# convertor_board.net
KiCad netlist of a schematic drawn in EAGLE
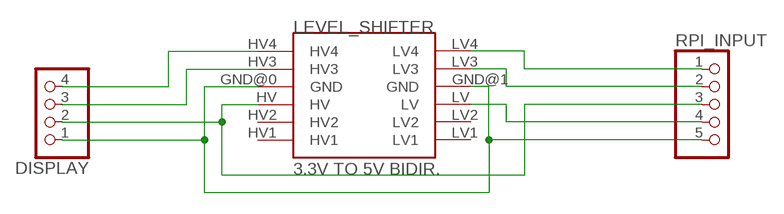
[diagram p0: schematic, sheet 1]

(export (version "E")
  (design (tool "Eeschema 10.0.6"))
  (components
    (comp (ref "DISPLAY")
      (value "PINHD-1X4")
      (footprint "eagle-import:1X04")
      (libsource (lib "eagle-import") (part "PINHD-1X4"))
    )
    (comp (ref "LEVEL_SHIFTER")
      (value "3.3V TO 5V BIDIR.")
      (footprint "eagle-import:LEVEL_SHIFTER")
      (libsource (lib "eagle-import") (part "LEVEL_SHIFTER"))
    )
    (comp (ref "RPI_INPUT")
      (value "PINHD-1X5")
      (footprint "eagle-import:1X05")
      (libsource (lib "eagle-import") (part "PINHD-1X5"))
    )
  )
  (nets
    (net (code "1") (name "Net-(DISPLAY-Pad1)") (class "Default")
      (node (ref "DISPLAY") (pin "1") (pinfunction "1_1") (pintype "passive"))
      (node (ref "LEVEL_SHIFTER") (pin "GND@0") (pinfunction "GND_GND@0") (pintype "bidirectional"))
      (node (ref "LEVEL_SHIFTER") (pin "GND@1") (pinfunction "GND_GND@1") (pintype "bidirectional"))
      (node (ref "RPI_INPUT") (pin "5") (pinfunction "5_5") (pintype "passive"))
    )
    (net (code "2") (name "Net-(DISPLAY-Pad2)") (class "Default")
      (node (ref "DISPLAY") (pin "2") (pinfunction "2_2") (pintype "passive"))
      (node (ref "LEVEL_SHIFTER") (pin "HV") (pinfunction "HV_HV") (pintype "bidirectional"))
      (node (ref "RPI_INPUT") (pin "3") (pinfunction "3_3") (pintype "passive"))
    )
    (net (code "3") (name "Net-(DISPLAY-Pad3)") (class "Default")
      (node (ref "DISPLAY") (pin "3") (pinfunction "3_3") (pintype "passive"))
      (node (ref "LEVEL_SHIFTER") (pin "HV3") (pinfunction "HV3_HV3") (pintype "bidirectional"))
    )
    (net (code "4") (name "Net-(DISPLAY-Pad4)") (class "Default")
      (node (ref "DISPLAY") (pin "4") (pinfunction "4_4") (pintype "passive"))
      (node (ref "LEVEL_SHIFTER") (pin "HV4") (pinfunction "HV4_HV4") (pintype "bidirectional"))
    )
    (net (code "5") (name "Net-(LEVEL_SHIFTER-PadLV)") (class "Default")
      (node (ref "LEVEL_SHIFTER") (pin "LV") (pinfunction "LV_LV") (pintype "bidirectional"))
      (node (ref "RPI_INPUT") (pin "4") (pinfunction "4_4") (pintype "passive"))
    )
    (net (code "6") (name "Net-(LEVEL_SHIFTER-PadLV3)") (class "Default")
      (node (ref "LEVEL_SHIFTER") (pin "LV3") (pinfunction "LV3_LV3") (pintype "bidirectional"))
      (node (ref "RPI_INPUT") (pin "2") (pinfunction "2_2") (pintype "passive"))
    )
    (net (code "7") (name "Net-(LEVEL_SHIFTER-PadLV4)") (class "Default")
      (node (ref "LEVEL_SHIFTER") (pin "LV4") (pinfunction "LV4_LV4") (pintype "bidirectional"))
      (node (ref "RPI_INPUT") (pin "1") (pinfunction "1_1") (pintype "passive"))
    )
    (net (code "8") (name "unconnected-(LEVEL_SHIFTER-PadHV1)") (class "Default")
      (node (ref "LEVEL_SHIFTER") (pin "HV1") (pinfunction "HV1_HV1") (pintype "bidirectional"))
    )
    (net (code "9") (name "unconnected-(LEVEL_SHIFTER-PadHV2)") (class "Default")
      (node (ref "LEVEL_SHIFTER") (pin "HV2") (pinfunction "HV2_HV2") (pintype "bidirectional"))
    )
    (net (code "10") (name "unconnected-(LEVEL_SHIFTER-PadLV1)") (class "Default")
      (node (ref "LEVEL_SHIFTER") (pin "LV1") (pinfunction "LV1_LV1") (pintype "bidirectional"))
    )
    (net (code "11") (name "unconnected-(LEVEL_SHIFTER-PadLV2)") (class "Default")
      (node (ref "LEVEL_SHIFTER") (pin "LV2") (pinfunction "LV2_LV2") (pintype "bidirectional"))
    )
  )
)
